# clock.net
KiCad netlist of a schematic drawn in EAGLE
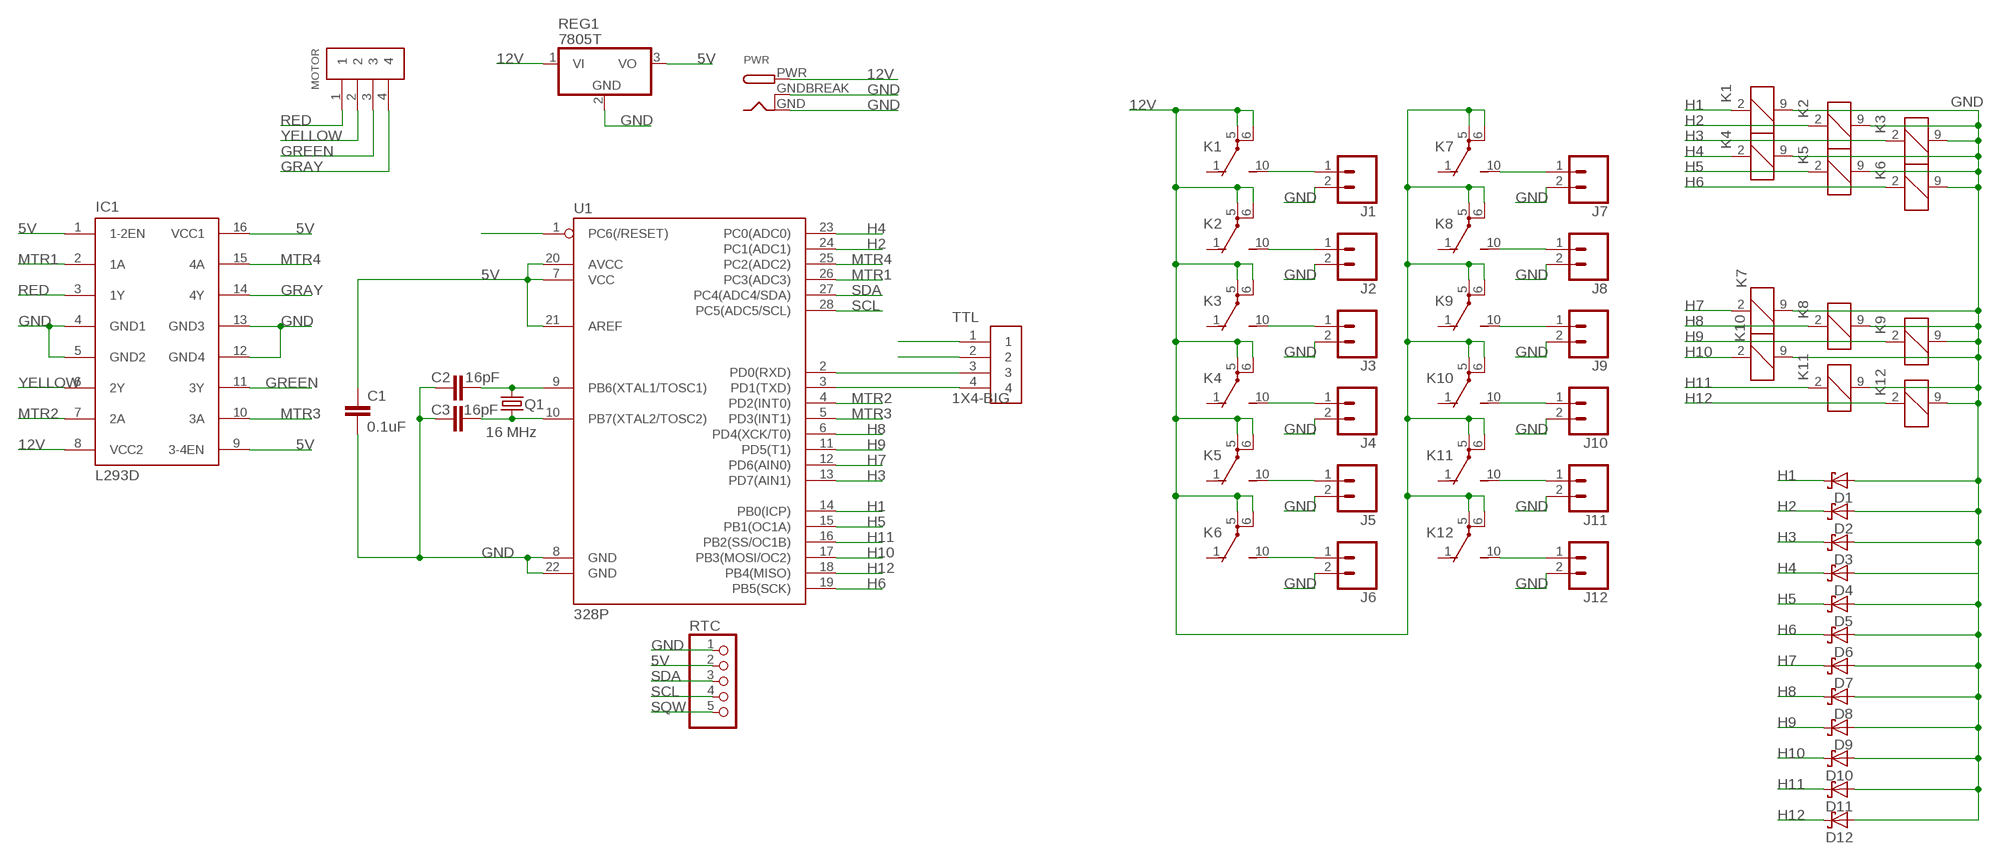
[diagram p0: schematic, sheet 1]

(export (version "E")
  (design (tool "Eeschema 10.0.6"))
  (components
    (comp (ref "C1")
      (value "0.1uF")
      (footprint "eagle-import:C1206")
      (libsource (lib "eagle-import") (part "C-EUC1206"))
    )
    (comp (ref "C2")
      (value "16pF")
      (footprint "eagle-import:C0805")
      (libsource (lib "eagle-import") (part "C-EUC0805"))
    )
    (comp (ref "C3")
      (value "16pF")
      (footprint "eagle-import:C0805")
      (libsource (lib "eagle-import") (part "C-EUC0805"))
    )
    (comp (ref "D1")
      (value "SCHOTTKY-DIODEDO41-7")
      (footprint "eagle-import:DO41-7")
      (libsource (lib "eagle-import") (part "SCHOTTKY-DIODEDO41-7"))
    )
    (comp (ref "D2")
      (value "SCHOTTKY-DIODEDO41-7")
      (footprint "eagle-import:DO41-7")
      (libsource (lib "eagle-import") (part "SCHOTTKY-DIODEDO41-7"))
    )
    (comp (ref "D3")
      (value "SCHOTTKY-DIODEDO41-7")
      (footprint "eagle-import:DO41-7")
      (libsource (lib "eagle-import") (part "SCHOTTKY-DIODEDO41-7"))
    )
    (comp (ref "D4")
      (value "SCHOTTKY-DIODEDO41-7")
      (footprint "eagle-import:DO41-7")
      (libsource (lib "eagle-import") (part "SCHOTTKY-DIODEDO41-7"))
    )
    (comp (ref "D5")
      (value "SCHOTTKY-DIODEDO41-7")
      (footprint "eagle-import:DO41-7")
      (libsource (lib "eagle-import") (part "SCHOTTKY-DIODEDO41-7"))
    )
    (comp (ref "D6")
      (value "SCHOTTKY-DIODEDO41-7")
      (footprint "eagle-import:DO41-7")
      (libsource (lib "eagle-import") (part "SCHOTTKY-DIODEDO41-7"))
    )
    (comp (ref "D7")
      (value "SCHOTTKY-DIODEDO41-7")
      (footprint "eagle-import:DO41-7")
      (libsource (lib "eagle-import") (part "SCHOTTKY-DIODEDO41-7"))
    )
    (comp (ref "D8")
      (value "SCHOTTKY-DIODEDO41-7")
      (footprint "eagle-import:DO41-7")
      (libsource (lib "eagle-import") (part "SCHOTTKY-DIODEDO41-7"))
    )
    (comp (ref "D9")
      (value "SCHOTTKY-DIODEDO41-7")
      (footprint "eagle-import:DO41-7")
      (libsource (lib "eagle-import") (part "SCHOTTKY-DIODEDO41-7"))
    )
    (comp (ref "D10")
      (value "SCHOTTKY-DIODEDO41-7")
      (footprint "eagle-import:DO41-7")
      (libsource (lib "eagle-import") (part "SCHOTTKY-DIODEDO41-7"))
    )
    (comp (ref "D11")
      (value "SCHOTTKY-DIODEDO41-7")
      (footprint "eagle-import:DO41-7")
      (libsource (lib "eagle-import") (part "SCHOTTKY-DIODEDO41-7"))
    )
    (comp (ref "D12")
      (value "SCHOTTKY-DIODEDO41-7")
      (footprint "eagle-import:DO41-7")
      (libsource (lib "eagle-import") (part "SCHOTTKY-DIODEDO41-7"))
    )
    (comp (ref "IC1")
      (value "L293D")
      (footprint "eagle-import:DIL16")
      (libsource (lib "eagle-import") (part "L293D"))
    )
    (comp (ref "J1")
      (value "CONN_02")
      (footprint "eagle-import:1X02")
      (libsource (lib "eagle-import") (part "CONN_02"))
    )
    (comp (ref "J2")
      (value "CONN_02")
      (footprint "eagle-import:1X02")
      (libsource (lib "eagle-import") (part "CONN_02"))
    )
    (comp (ref "J3")
      (value "CONN_02")
      (footprint "eagle-import:1X02")
      (libsource (lib "eagle-import") (part "CONN_02"))
    )
    (comp (ref "J4")
      (value "CONN_02")
      (footprint "eagle-import:1X02")
      (libsource (lib "eagle-import") (part "CONN_02"))
    )
    (comp (ref "J5")
      (value "CONN_02")
      (footprint "eagle-import:1X02")
      (libsource (lib "eagle-import") (part "CONN_02"))
    )
    (comp (ref "J6")
      (value "CONN_02")
      (footprint "eagle-import:1X02")
      (libsource (lib "eagle-import") (part "CONN_02"))
    )
    (comp (ref "J7")
      (value "CONN_02")
      (footprint "eagle-import:1X02")
      (libsource (lib "eagle-import") (part "CONN_02"))
    )
    (comp (ref "J8")
      (value "CONN_02")
      (footprint "eagle-import:1X02")
      (libsource (lib "eagle-import") (part "CONN_02"))
    )
    (comp (ref "J9")
      (value "CONN_02")
      (footprint "eagle-import:1X02")
      (libsource (lib "eagle-import") (part "CONN_02"))
    )
    (comp (ref "J10")
      (value "CONN_02")
      (footprint "eagle-import:1X02")
      (libsource (lib "eagle-import") (part "CONN_02"))
    )
    (comp (ref "J11")
      (value "CONN_02")
      (footprint "eagle-import:1X02")
      (libsource (lib "eagle-import") (part "CONN_02"))
    )
    (comp (ref "J12")
      (value "CONN_02")
      (footprint "eagle-import:1X02")
      (libsource (lib "eagle-import") (part "CONN_02"))
    )
    (comp (ref "K1")
      (value "G5V1")
      (footprint "eagle-import:G5V1")
      (fields (field (name "MPN") "G5V-1-DC24"))
      (libsource (lib "eagle-import") (part "G5V1"))
    )
    (comp (ref "K2")
      (value "G5V1")
      (footprint "eagle-import:G5V1")
      (fields (field (name "MPN") "G5V-1-DC24"))
      (libsource (lib "eagle-import") (part "G5V1"))
    )
    (comp (ref "K3")
      (value "G5V1")
      (footprint "eagle-import:G5V1")
      (fields (field (name "MPN") "G5V-1-DC24"))
      (libsource (lib "eagle-import") (part "G5V1"))
    )
    (comp (ref "K4")
      (value "G5V1")
      (footprint "eagle-import:G5V1")
      (fields (field (name "MPN") "G5V-1-DC24"))
      (libsource (lib "eagle-import") (part "G5V1"))
    )
    (comp (ref "K5")
      (value "G5V1")
      (footprint "eagle-import:G5V1")
      (fields (field (name "MPN") "G5V-1-DC24"))
      (libsource (lib "eagle-import") (part "G5V1"))
    )
    (comp (ref "K6")
      (value "G5V1")
      (footprint "eagle-import:G5V1")
      (fields (field (name "MPN") "G5V-1-DC24"))
      (libsource (lib "eagle-import") (part "G5V1"))
    )
    (comp (ref "K7")
      (value "G5V1")
      (footprint "eagle-import:G5V1")
      (fields (field (name "MPN") "G5V-1-DC24"))
      (libsource (lib "eagle-import") (part "G5V1"))
    )
    (comp (ref "K8")
      (value "G5V1")
      (footprint "eagle-import:G5V1")
      (fields (field (name "MPN") "G5V-1-DC24"))
      (libsource (lib "eagle-import") (part "G5V1"))
    )
    (comp (ref "K9")
      (value "G5V1")
      (footprint "eagle-import:G5V1")
      (fields (field (name "MPN") "G5V-1-DC24"))
      (libsource (lib "eagle-import") (part "G5V1"))
    )
    (comp (ref "K10")
      (value "G5V1")
      (footprint "eagle-import:G5V1")
      (fields (field (name "MPN") "G5V-1-DC24"))
      (libsource (lib "eagle-import") (part "G5V1"))
    )
    (comp (ref "K11")
      (value "G5V1")
      (footprint "eagle-import:G5V1")
      (fields (field (name "MPN") "G5V-1-DC24"))
      (libsource (lib "eagle-import") (part "G5V1"))
    )
    (comp (ref "K12")
      (value "G5V1")
      (footprint "eagle-import:G5V1")
      (fields (field (name "MPN") "G5V-1-DC24"))
      (libsource (lib "eagle-import") (part "G5V1"))
    )
    (comp (ref "MOTOR")
      (value "1X4-BIG")
      (footprint "eagle-import:1X04-BIG")
      (libsource (lib "eagle-import") (part "1X4-BIG"))
    )
    (comp (ref "PWR")
      (value "DCBARRELPTH")
      (footprint "eagle-import:DCJACK_2MM_PTH")
      (libsource (lib "eagle-import") (part "DCBARRELPTH"))
    )
    (comp (ref "Q1")
      (value "16 MHz")
      (footprint "eagle-import:HC49_S")
      (libsource (lib "eagle-import") (part "CRYSTALHC49S"))
    )
    (comp (ref "REG1")
      (value "7805T")
      (footprint "eagle-import:TO220H")
      (libsource (lib "eagle-import") (part "78T05"))
    )
    (comp (ref "RTC")
      (value "PINHD-1X5")
      (footprint "eagle-import:1X05")
      (libsource (lib "eagle-import") (part "PINHD-1X5"))
    )
    (comp (ref "TTL")
      (value "1X4-BIG")
      (footprint "eagle-import:1X04-BIG")
      (libsource (lib "eagle-import") (part "1X4-BIG"))
    )
    (comp (ref "U1")
      (value "328P")
      (footprint "eagle-import:DIP28")
      (libsource (lib "eagle-import") (part "ATMEGA328P_PDIP"))
    )
  )
  (nets
    (net (code "1") (name "/5V") (class "Default")
      (node (ref "C1") (pin "1") (pinfunction "1_1") (pintype "passive"))
      (node (ref "IC1") (pin "1") (pinfunction "1-2EN_1") (pintype "input"))
      (node (ref "IC1") (pin "16") (pinfunction "VCC1_16") (pintype "power_in"))
      (node (ref "IC1") (pin "9") (pinfunction "3-4EN_9") (pintype "input"))
      (node (ref "REG1") (pin "3") (pinfunction "VO_3") (pintype "passive"))
      (node (ref "RTC") (pin "2") (pinfunction "2_2") (pintype "passive"))
      (node (ref "U1") (pin "20") (pinfunction "AVCC_20") (pintype "bidirectional"))
      (node (ref "U1") (pin "21") (pinfunction "AREF_21") (pintype "bidirectional"))
      (node (ref "U1") (pin "7") (pinfunction "VCC_7") (pintype "bidirectional"))
    )
    (net (code "2") (name "/12V") (class "Default")
      (node (ref "IC1") (pin "8") (pinfunction "VCC2_8") (pintype "power_in"))
      (node (ref "K1") (pin "5") (pinfunction "P_5") (pintype "passive"))
      (node (ref "K1") (pin "6") (pinfunction "P_6") (pintype "passive"))
      (node (ref "K10") (pin "5") (pinfunction "P_5") (pintype "passive"))
      (node (ref "K10") (pin "6") (pinfunction "P_6") (pintype "passive"))
      (node (ref "K11") (pin "5") (pinfunction "P_5") (pintype "passive"))
      (node (ref "K11") (pin "6") (pinfunction "P_6") (pintype "passive"))
      (node (ref "K12") (pin "5") (pinfunction "P_5") (pintype "passive"))
      (node (ref "K12") (pin "6") (pinfunction "P_6") (pintype "passive"))
      (node (ref "K2") (pin "5") (pinfunction "P_5") (pintype "passive"))
      (node (ref "K2") (pin "6") (pinfunction "P_6") (pintype "passive"))
      (node (ref "K3") (pin "5") (pinfunction "P_5") (pintype "passive"))
      (node (ref "K3") (pin "6") (pinfunction "P_6") (pintype "passive"))
      (node (ref "K4") (pin "5") (pinfunction "P_5") (pintype "passive"))
      (node (ref "K4") (pin "6") (pinfunction "P_6") (pintype "passive"))
      (node (ref "K5") (pin "5") (pinfunction "P_5") (pintype "passive"))
      (node (ref "K5") (pin "6") (pinfunction "P_6") (pintype "passive"))
      (node (ref "K6") (pin "5") (pinfunction "P_5") (pintype "passive"))
      (node (ref "K6") (pin "6") (pinfunction "P_6") (pintype "passive"))
      (node (ref "K7") (pin "5") (pinfunction "P_5") (pintype "passive"))
      (node (ref "K7") (pin "6") (pinfunction "P_6") (pintype "passive"))
      (node (ref "K8") (pin "5") (pinfunction "P_5") (pintype "passive"))
      (node (ref "K8") (pin "6") (pinfunction "P_6") (pintype "passive"))
      (node (ref "K9") (pin "5") (pinfunction "P_5") (pintype "passive"))
      (node (ref "K9") (pin "6") (pinfunction "P_6") (pintype "passive"))
      (node (ref "PWR") (pin "PWR") (pinfunction "PWR_PWR") (pintype "power_in"))
      (node (ref "REG1") (pin "1") (pinfunction "VI_1") (pintype "input"))
    )
    (net (code "3") (name "/GND") (class "Default")
      (node (ref "C1") (pin "2") (pinfunction "2_2") (pintype "passive"))
      (node (ref "C2") (pin "1") (pinfunction "1_1") (pintype "passive"))
      (node (ref "C3") (pin "1") (pinfunction "1_1") (pintype "passive"))
      (node (ref "D1") (pin "A") (pinfunction "A_A") (pintype "passive"))
      (node (ref "D10") (pin "A") (pinfunction "A_A") (pintype "passive"))
      (node (ref "D11") (pin "A") (pinfunction "A_A") (pintype "passive"))
      (node (ref "D12") (pin "A") (pinfunction "A_A") (pintype "passive"))
      (node (ref "D2") (pin "A") (pinfunction "A_A") (pintype "passive"))
      (node (ref "D3") (pin "A") (pinfunction "A_A") (pintype "passive"))
      (node (ref "D4") (pin "A") (pinfunction "A_A") (pintype "passive"))
      (node (ref "D5") (pin "A") (pinfunction "A_A") (pintype "passive"))
      (node (ref "D6") (pin "A") (pinfunction "A_A") (pintype "passive"))
      (node (ref "D7") (pin "A") (pinfunction "A_A") (pintype "passive"))
      (node (ref "D8") (pin "A") (pinfunction "A_A") (pintype "passive"))
      (node (ref "D9") (pin "A") (pinfunction "A_A") (pintype "passive"))
      (node (ref "IC1") (pin "12") (pinfunction "GND4_12") (pintype "power_in"))
      (node (ref "IC1") (pin "13") (pinfunction "GND3_13") (pintype "power_in"))
      (node (ref "IC1") (pin "4") (pinfunction "GND1_4") (pintype "power_in"))
      (node (ref "IC1") (pin "5") (pinfunction "GND2_5") (pintype "power_in"))
      (node (ref "J1") (pin "2") (pinfunction "2_2") (pintype "passive"))
      (node (ref "J10") (pin "2") (pinfunction "2_2") (pintype "passive"))
      (node (ref "J11") (pin "2") (pinfunction "2_2") (pintype "passive"))
      (node (ref "J12") (pin "2") (pinfunction "2_2") (pintype "passive"))
      (node (ref "J2") (pin "2") (pinfunction "2_2") (pintype "passive"))
      (node (ref "J3") (pin "2") (pinfunction "2_2") (pintype "passive"))
      (node (ref "J4") (pin "2") (pinfunction "2_2") (pintype "passive"))
      (node (ref "J5") (pin "2") (pinfunction "2_2") (pintype "passive"))
      (node (ref "J6") (pin "2") (pinfunction "2_2") (pintype "passive"))
      (node (ref "J7") (pin "2") (pinfunction "2_2") (pintype "passive"))
      (node (ref "J8") (pin "2") (pinfunction "2_2") (pintype "passive"))
      (node (ref "J9") (pin "2") (pinfunction "2_2") (pintype "passive"))
      (node (ref "K1") (pin "9") (pinfunction "2_9") (pintype "passive"))
      (node (ref "K10") (pin "9") (pinfunction "2_9") (pintype "passive"))
      (node (ref "K11") (pin "9") (pinfunction "2_9") (pintype "passive"))
      (node (ref "K12") (pin "9") (pinfunction "2_9") (pintype "passive"))
      (node (ref "K2") (pin "9") (pinfunction "2_9") (pintype "passive"))
      (node (ref "K3") (pin "9") (pinfunction "2_9") (pintype "passive"))
      (node (ref "K4") (pin "9") (pinfunction "2_9") (pintype "passive"))
      (node (ref "K5") (pin "9") (pinfunction "2_9") (pintype "passive"))
      (node (ref "K6") (pin "9") (pinfunction "2_9") (pintype "passive"))
      (node (ref "K7") (pin "9") (pinfunction "2_9") (pintype "passive"))
      (node (ref "K8") (pin "9") (pinfunction "2_9") (pintype "passive"))
      (node (ref "K9") (pin "9") (pinfunction "2_9") (pintype "passive"))
      (node (ref "PWR") (pin "GND") (pinfunction "GND_GND") (pintype "power_in"))
      (node (ref "PWR") (pin "GNDBREAK") (pinfunction "GNDBREAK_GNDBREAK") (pintype "power_in"))
      (node (ref "REG1") (pin "2") (pinfunction "GND_2") (pintype "passive"))
      (node (ref "RTC") (pin "1") (pinfunction "1_1") (pintype "passive"))
      (node (ref "U1") (pin "22") (pinfunction "GND_22") (pintype "bidirectional"))
      (node (ref "U1") (pin "8") (pinfunction "GND_8") (pintype "bidirectional"))
    )
    (net (code "4") (name "/GRAY") (class "Default")
      (node (ref "IC1") (pin "14") (pinfunction "4Y_14") (pintype "output"))
      (node (ref "MOTOR") (pin "4") (pinfunction "4_4") (pintype "bidirectional"))
    )
    (net (code "5") (name "/GREEN") (class "Default")
      (node (ref "IC1") (pin "11") (pinfunction "3Y_11") (pintype "output"))
      (node (ref "MOTOR") (pin "3") (pinfunction "3_3") (pintype "bidirectional"))
    )
    (net (code "6") (name "/H1") (class "Default")
      (node (ref "D1") (pin "C") (pinfunction "C_C") (pintype "passive"))
      (node (ref "K1") (pin "2") (pinfunction "1_2") (pintype "passive"))
      (node (ref "U1") (pin "14") (pinfunction "PB0(ICP)_14") (pintype "bidirectional"))
    )
    (net (code "7") (name "/H2") (class "Default")
      (node (ref "D2") (pin "C") (pinfunction "C_C") (pintype "passive"))
      (node (ref "K2") (pin "2") (pinfunction "1_2") (pintype "passive"))
      (node (ref "U1") (pin "24") (pinfunction "PC1(ADC1)_24") (pintype "bidirectional"))
    )
    (net (code "8") (name "/H3") (class "Default")
      (node (ref "D3") (pin "C") (pinfunction "C_C") (pintype "passive"))
      (node (ref "K3") (pin "2") (pinfunction "1_2") (pintype "passive"))
      (node (ref "U1") (pin "13") (pinfunction "PD7(AIN1)_13") (pintype "bidirectional"))
    )
    (net (code "9") (name "/H4") (class "Default")
      (node (ref "D4") (pin "C") (pinfunction "C_C") (pintype "passive"))
      (node (ref "K4") (pin "2") (pinfunction "1_2") (pintype "passive"))
      (node (ref "U1") (pin "23") (pinfunction "PC0(ADC0)_23") (pintype "bidirectional"))
    )
    (net (code "10") (name "/H5") (class "Default")
      (node (ref "D5") (pin "C") (pinfunction "C_C") (pintype "passive"))
      (node (ref "K5") (pin "2") (pinfunction "1_2") (pintype "passive"))
      (node (ref "U1") (pin "15") (pinfunction "PB1(OC1A)_15") (pintype "bidirectional"))
    )
    (net (code "11") (name "/H6") (class "Default")
      (node (ref "D6") (pin "C") (pinfunction "C_C") (pintype "passive"))
      (node (ref "K6") (pin "2") (pinfunction "1_2") (pintype "passive"))
      (node (ref "U1") (pin "19") (pinfunction "PB5(SCK)_19") (pintype "bidirectional"))
    )
    (net (code "12") (name "/H7") (class "Default")
      (node (ref "D7") (pin "C") (pinfunction "C_C") (pintype "passive"))
      (node (ref "K7") (pin "2") (pinfunction "1_2") (pintype "passive"))
      (node (ref "U1") (pin "12") (pinfunction "PD6(AIN0)_12") (pintype "bidirectional"))
    )
    (net (code "13") (name "/H8") (class "Default")
      (node (ref "D8") (pin "C") (pinfunction "C_C") (pintype "passive"))
      (node (ref "K8") (pin "2") (pinfunction "1_2") (pintype "passive"))
      (node (ref "U1") (pin "6") (pinfunction "PD4(XCK/T0)_6") (pintype "bidirectional"))
    )
    (net (code "14") (name "/H9") (class "Default")
      (node (ref "D9") (pin "C") (pinfunction "C_C") (pintype "passive"))
      (node (ref "K9") (pin "2") (pinfunction "1_2") (pintype "passive"))
      (node (ref "U1") (pin "11") (pinfunction "PD5(T1)_11") (pintype "bidirectional"))
    )
    (net (code "15") (name "/H10") (class "Default")
      (node (ref "D10") (pin "C") (pinfunction "C_C") (pintype "passive"))
      (node (ref "K10") (pin "2") (pinfunction "1_2") (pintype "passive"))
      (node (ref "U1") (pin "17") (pinfunction "PB3(MOSI/OC2)_17") (pintype "bidirectional"))
    )
    (net (code "16") (name "/H11") (class "Default")
      (node (ref "D11") (pin "C") (pinfunction "C_C") (pintype "passive"))
      (node (ref "K11") (pin "2") (pinfunction "1_2") (pintype "passive"))
      (node (ref "U1") (pin "16") (pinfunction "PB2(SS/OC1B)_16") (pintype "bidirectional"))
    )
    (net (code "17") (name "/H12") (class "Default")
      (node (ref "D12") (pin "C") (pinfunction "C_C") (pintype "passive"))
      (node (ref "K12") (pin "2") (pinfunction "1_2") (pintype "passive"))
      (node (ref "U1") (pin "18") (pinfunction "PB4(MISO)_18") (pintype "bidirectional"))
    )
    (net (code "18") (name "/MTR1") (class "Default")
      (node (ref "IC1") (pin "2") (pinfunction "1A_2") (pintype "input"))
      (node (ref "U1") (pin "26") (pinfunction "PC3(ADC3)_26") (pintype "bidirectional"))
    )
    (net (code "19") (name "/MTR2") (class "Default")
      (node (ref "IC1") (pin "7") (pinfunction "2A_7") (pintype "input"))
      (node (ref "U1") (pin "4") (pinfunction "PD2(INT0)_4") (pintype "bidirectional"))
    )
    (net (code "20") (name "/MTR3") (class "Default")
      (node (ref "IC1") (pin "10") (pinfunction "3A_10") (pintype "input"))
      (node (ref "U1") (pin "5") (pinfunction "PD3(INT1)_5") (pintype "bidirectional"))
    )
    (net (code "21") (name "/MTR4") (class "Default")
      (node (ref "IC1") (pin "15") (pinfunction "4A_15") (pintype "input"))
      (node (ref "U1") (pin "25") (pinfunction "PC2(ADC2)_25") (pintype "bidirectional"))
    )
    (net (code "22") (name "/RED") (class "Default")
      (node (ref "IC1") (pin "3") (pinfunction "1Y_3") (pintype "output"))
      (node (ref "MOTOR") (pin "1") (pinfunction "1_1") (pintype "bidirectional"))
    )
    (net (code "23") (name "/SCL") (class "Default")
      (node (ref "RTC") (pin "4") (pinfunction "4_4") (pintype "passive"))
      (node (ref "U1") (pin "28") (pinfunction "PC5(ADC5/SCL)_28") (pintype "bidirectional"))
    )
    (net (code "24") (name "/SDA") (class "Default")
      (node (ref "RTC") (pin "3") (pinfunction "3_3") (pintype "passive"))
      (node (ref "U1") (pin "27") (pinfunction "PC4(ADC4/SDA)_27") (pintype "bidirectional"))
    )
    (net (code "25") (name "/SQW") (class "Default")
      (node (ref "RTC") (pin "5") (pinfunction "5_5") (pintype "passive"))
    )
    (net (code "26") (name "/YELLOW") (class "Default")
      (node (ref "IC1") (pin "6") (pinfunction "2Y_6") (pintype "output"))
      (node (ref "MOTOR") (pin "2") (pinfunction "2_2") (pintype "bidirectional"))
    )
    (net (code "27") (name "Net-(K1B-S)") (class "Default")
      (node (ref "J1") (pin "1") (pinfunction "1_1") (pintype "passive"))
      (node (ref "K1") (pin "10") (pinfunction "S_10") (pintype "passive"))
    )
    (net (code "28") (name "Net-(K2B-S)") (class "Default")
      (node (ref "J2") (pin "1") (pinfunction "1_1") (pintype "passive"))
      (node (ref "K2") (pin "10") (pinfunction "S_10") (pintype "passive"))
    )
    (net (code "29") (name "Net-(K3B-S)") (class "Default")
      (node (ref "J3") (pin "1") (pinfunction "1_1") (pintype "passive"))
      (node (ref "K3") (pin "10") (pinfunction "S_10") (pintype "passive"))
    )
    (net (code "30") (name "Net-(K4B-S)") (class "Default")
      (node (ref "J4") (pin "1") (pinfunction "1_1") (pintype "passive"))
      (node (ref "K4") (pin "10") (pinfunction "S_10") (pintype "passive"))
    )
    (net (code "31") (name "Net-(K5B-S)") (class "Default")
      (node (ref "J5") (pin "1") (pinfunction "1_1") (pintype "passive"))
      (node (ref "K5") (pin "10") (pinfunction "S_10") (pintype "passive"))
    )
    (net (code "32") (name "Net-(K6B-S)") (class "Default")
      (node (ref "J6") (pin "1") (pinfunction "1_1") (pintype "passive"))
      (node (ref "K6") (pin "10") (pinfunction "S_10") (pintype "passive"))
    )
    (net (code "33") (name "Net-(K7B-S)") (class "Default")
      (node (ref "J7") (pin "1") (pinfunction "1_1") (pintype "passive"))
      (node (ref "K7") (pin "10") (pinfunction "S_10") (pintype "passive"))
    )
    (net (code "34") (name "Net-(K8B-S)") (class "Default")
      (node (ref "J8") (pin "1") (pinfunction "1_1") (pintype "passive"))
      (node (ref "K8") (pin "10") (pinfunction "S_10") (pintype "passive"))
    )
    (net (code "35") (name "Net-(K9B-S)") (class "Default")
      (node (ref "J9") (pin "1") (pinfunction "1_1") (pintype "passive"))
      (node (ref "K9") (pin "10") (pinfunction "S_10") (pintype "passive"))
    )
    (net (code "36") (name "Net-(K10B-S)") (class "Default")
      (node (ref "J10") (pin "1") (pinfunction "1_1") (pintype "passive"))
      (node (ref "K10") (pin "10") (pinfunction "S_10") (pintype "passive"))
    )
    (net (code "37") (name "Net-(K11B-S)") (class "Default")
      (node (ref "J11") (pin "1") (pinfunction "1_1") (pintype "passive"))
      (node (ref "K11") (pin "10") (pinfunction "S_10") (pintype "passive"))
    )
    (net (code "38") (name "Net-(K12B-S)") (class "Default")
      (node (ref "J12") (pin "1") (pinfunction "1_1") (pintype "passive"))
      (node (ref "K12") (pin "10") (pinfunction "S_10") (pintype "passive"))
    )
    (net (code "39") (name "Net-(U1-PB6(XTAL1{slash}TOSC1))") (class "Default")
      (node (ref "C2") (pin "2") (pinfunction "2_2") (pintype "passive"))
      (node (ref "Q1") (pin "2") (pinfunction "2_2") (pintype "passive"))
      (node (ref "U1") (pin "9") (pinfunction "PB6(XTAL1/TOSC1)_9") (pintype "bidirectional"))
    )
    (net (code "40") (name "Net-(U1-PB7(XTAL2{slash}TOSC2))") (class "Default")
      (node (ref "C3") (pin "2") (pinfunction "2_2") (pintype "passive"))
      (node (ref "Q1") (pin "1") (pinfunction "1_1") (pintype "passive"))
      (node (ref "U1") (pin "10") (pinfunction "PB7(XTAL2/TOSC2)_10") (pintype "bidirectional"))
    )
    (net (code "41") (name "Net-(U1-PD0(RXD))") (class "Default")
      (node (ref "TTL") (pin "3") (pinfunction "3_3") (pintype "bidirectional"))
      (node (ref "U1") (pin "2") (pinfunction "PD0(RXD)_2") (pintype "bidirectional"))
    )
    (net (code "42") (name "Net-(U1-PD1(TXD))") (class "Default")
      (node (ref "TTL") (pin "4") (pinfunction "4_4") (pintype "bidirectional"))
      (node (ref "U1") (pin "3") (pinfunction "PD1(TXD)_3") (pintype "bidirectional"))
    )
    (net (code "43") (name "unconnected-(K1B-O-Pad1)") (class "Default")
      (node (ref "K1") (pin "1") (pinfunction "O_1") (pintype "passive"))
    )
    (net (code "44") (name "unconnected-(K2B-O-Pad1)") (class "Default")
      (node (ref "K2") (pin "1") (pinfunction "O_1") (pintype "passive"))
    )
    (net (code "45") (name "unconnected-(K3B-O-Pad1)") (class "Default")
      (node (ref "K3") (pin "1") (pinfunction "O_1") (pintype "passive"))
    )
    (net (code "46") (name "unconnected-(K4B-O-Pad1)") (class "Default")
      (node (ref "K4") (pin "1") (pinfunction "O_1") (pintype "passive"))
    )
    (net (code "47") (name "unconnected-(K5B-O-Pad1)") (class "Default")
      (node (ref "K5") (pin "1") (pinfunction "O_1") (pintype "passive"))
    )
    (net (code "48") (name "unconnected-(K6B-O-Pad1)") (class "Default")
      (node (ref "K6") (pin "1") (pinfunction "O_1") (pintype "passive"))
    )
    (net (code "49") (name "unconnected-(K7B-O-Pad1)") (class "Default")
      (node (ref "K7") (pin "1") (pinfunction "O_1") (pintype "passive"))
    )
    (net (code "50") (name "unconnected-(K8B-O-Pad1)") (class "Default")
      (node (ref "K8") (pin "1") (pinfunction "O_1") (pintype "passive"))
    )
    (net (code "51") (name "unconnected-(K9B-O-Pad1)") (class "Default")
      (node (ref "K9") (pin "1") (pinfunction "O_1") (pintype "passive"))
    )
    (net (code "52") (name "unconnected-(K10B-O-Pad1)") (class "Default")
      (node (ref "K10") (pin "1") (pinfunction "O_1") (pintype "passive"))
    )
    (net (code "53") (name "unconnected-(K11B-O-Pad1)") (class "Default")
      (node (ref "K11") (pin "1") (pinfunction "O_1") (pintype "passive"))
    )
    (net (code "54") (name "unconnected-(K12B-O-Pad1)") (class "Default")
      (node (ref "K12") (pin "1") (pinfunction "O_1") (pintype "passive"))
    )
    (net (code "55") (name "unconnected-(TTL-Pad1)") (class "Default")
      (node (ref "TTL") (pin "1") (pinfunction "1_1") (pintype "bidirectional"))
    )
    (net (code "56") (name "unconnected-(TTL-Pad2)") (class "Default")
      (node (ref "TTL") (pin "2") (pinfunction "2_2") (pintype "bidirectional"))
    )
    (net (code "57") (name "unconnected-(U1-PC6({slash}RESET)-Pad1)") (class "Default")
      (node (ref "U1") (pin "1") (pinfunction "PC6(/RESET)_1") (pintype "bidirectional"))
    )
  )
)
